# High_Voltage_H-Bridge.net
KiCad netlist of a schematic drawn in Altium Designer
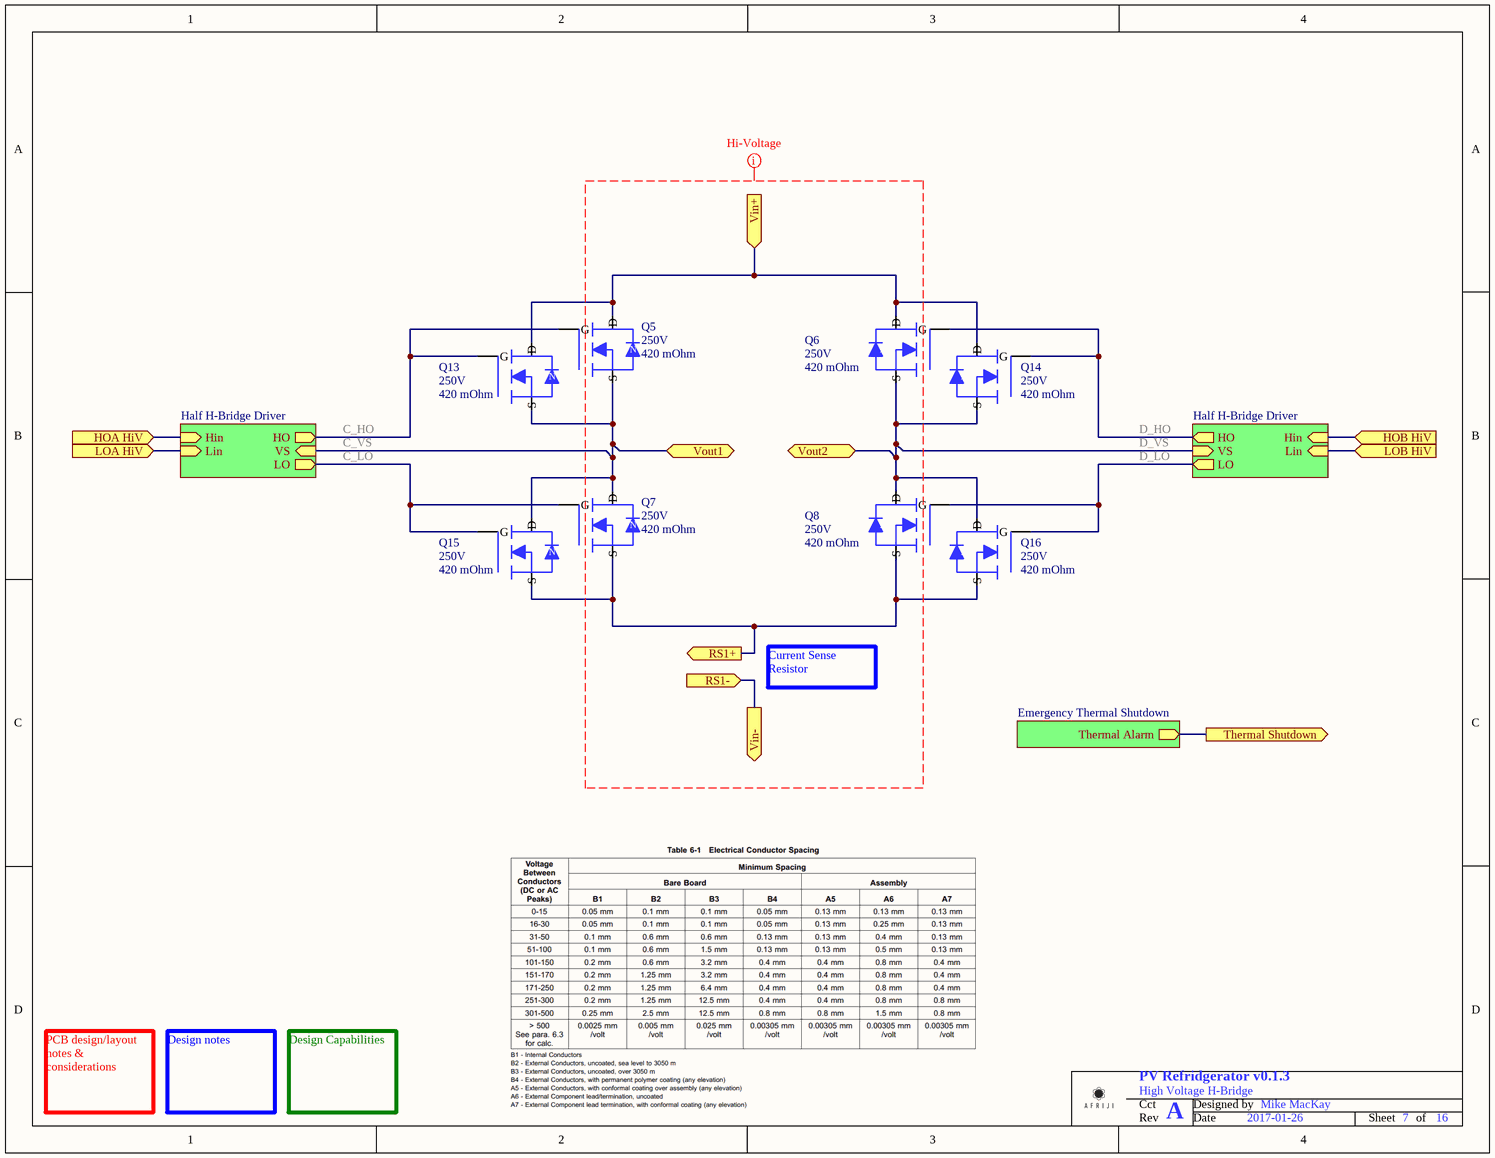
[diagram p0: High Voltage H-Bridge.SchDoc]

(export (version "E")
  (design (tool "Eeschema 10.0.6"))
  (components
    (comp (ref "Q5")
      (value "N-MOSFET 420mR 250V")
      (footprint "DPAK")
      (fields
        (field (name "MANUFACTURER") "Fairchild/ON Semiconductor")
        (field (name "MANUFACTURER PART NUMBER") "FQD9N25TM")
        (field (name "DRAIN TO SOURCE VOLTAGE (VDSS)") "250V")
        (field (name "RDS ON (MAX) @ ID, VGS") "420 mOhm")
      )
      (libsource (lib "Local Library") (part "N-MOSFET 420mR 250V"))
    )
    (comp (ref "Q6")
      (value "N-MOSFET 420mR 250V")
      (footprint "DPAK")
      (fields
        (field (name "MANUFACTURER") "Fairchild/ON Semiconductor")
        (field (name "MANUFACTURER PART NUMBER") "FQD9N25TM")
        (field (name "DRAIN TO SOURCE VOLTAGE (VDSS)") "250V")
        (field (name "RDS ON (MAX) @ ID, VGS") "420 mOhm")
      )
      (libsource (lib "Local Library") (part "N-MOSFET 420mR 250V"))
    )
    (comp (ref "Q7")
      (value "N-MOSFET 420mR 250V")
      (footprint "DPAK")
      (fields
        (field (name "MANUFACTURER") "Fairchild/ON Semiconductor")
        (field (name "MANUFACTURER PART NUMBER") "FQD9N25TM")
        (field (name "DRAIN TO SOURCE VOLTAGE (VDSS)") "250V")
        (field (name "RDS ON (MAX) @ ID, VGS") "420 mOhm")
      )
      (libsource (lib "Local Library") (part "N-MOSFET 420mR 250V"))
    )
    (comp (ref "Q8")
      (value "N-MOSFET 420mR 250V")
      (footprint "DPAK")
      (fields
        (field (name "MANUFACTURER") "Fairchild/ON Semiconductor")
        (field (name "MANUFACTURER PART NUMBER") "FQD9N25TM")
        (field (name "DRAIN TO SOURCE VOLTAGE (VDSS)") "250V")
        (field (name "RDS ON (MAX) @ ID, VGS") "420 mOhm")
      )
      (libsource (lib "Local Library") (part "N-MOSFET 420mR 250V"))
    )
    (comp (ref "Q13")
      (value "N-MOSFET 420mR 250V")
      (footprint "DPAK")
      (fields
        (field (name "MANUFACTURER") "Fairchild/ON Semiconductor")
        (field (name "MANUFACTURER PART NUMBER") "FQD9N25TM")
        (field (name "DRAIN TO SOURCE VOLTAGE (VDSS)") "250V")
        (field (name "RDS ON (MAX) @ ID, VGS") "420 mOhm")
      )
      (libsource (lib "Local Library") (part "N-MOSFET 420mR 250V"))
    )
    (comp (ref "Q14")
      (value "N-MOSFET 420mR 250V")
      (footprint "DPAK")
      (fields
        (field (name "MANUFACTURER") "Fairchild/ON Semiconductor")
        (field (name "MANUFACTURER PART NUMBER") "FQD9N25TM")
        (field (name "DRAIN TO SOURCE VOLTAGE (VDSS)") "250V")
        (field (name "RDS ON (MAX) @ ID, VGS") "420 mOhm")
      )
      (libsource (lib "Local Library") (part "N-MOSFET 420mR 250V"))
    )
    (comp (ref "Q15")
      (value "N-MOSFET 420mR 250V")
      (footprint "DPAK")
      (fields
        (field (name "MANUFACTURER") "Fairchild/ON Semiconductor")
        (field (name "MANUFACTURER PART NUMBER") "FQD9N25TM")
        (field (name "DRAIN TO SOURCE VOLTAGE (VDSS)") "250V")
        (field (name "RDS ON (MAX) @ ID, VGS") "420 mOhm")
      )
      (libsource (lib "Local Library") (part "N-MOSFET 420mR 250V"))
    )
    (comp (ref "Q16")
      (value "N-MOSFET 420mR 250V")
      (footprint "DPAK")
      (fields
        (field (name "MANUFACTURER") "Fairchild/ON Semiconductor")
        (field (name "MANUFACTURER PART NUMBER") "FQD9N25TM")
        (field (name "DRAIN TO SOURCE VOLTAGE (VDSS)") "250V")
        (field (name "RDS ON (MAX) @ ID, VGS") "420 mOhm")
      )
      (libsource (lib "Local Library") (part "N-MOSFET 420mR 250V"))
    )
  )
  (nets
    (net (code "1") (name "/C_HO") (class "Default")
      (node (ref "Q13") (pin "1") (pinfunction "G_1") (pintype "passive"))
      (node (ref "Q5") (pin "1") (pinfunction "G_1") (pintype "passive"))
    )
    (net (code "2") (name "/C_LO") (class "Default")
      (node (ref "Q15") (pin "1") (pinfunction "G_1") (pintype "passive"))
      (node (ref "Q7") (pin "1") (pinfunction "G_1") (pintype "passive"))
    )
    (net (code "3") (name "/C_VS") (class "Default")
      (node (ref "Q13") (pin "3") (pinfunction "S_3") (pintype "passive"))
      (node (ref "Q15") (pin "2") (pinfunction "D_2") (pintype "passive"))
      (node (ref "Q5") (pin "3") (pinfunction "S_3") (pintype "passive"))
      (node (ref "Q7") (pin "2") (pinfunction "D_2") (pintype "passive"))
    )
    (net (code "4") (name "/D_HO") (class "Default")
      (node (ref "Q14") (pin "1") (pinfunction "G_1") (pintype "passive"))
      (node (ref "Q6") (pin "1") (pinfunction "G_1") (pintype "passive"))
    )
    (net (code "5") (name "/D_LO") (class "Default")
      (node (ref "Q16") (pin "1") (pinfunction "G_1") (pintype "passive"))
      (node (ref "Q8") (pin "1") (pinfunction "G_1") (pintype "passive"))
    )
    (net (code "6") (name "/D_VS") (class "Default")
      (node (ref "Q14") (pin "3") (pinfunction "S_3") (pintype "passive"))
      (node (ref "Q16") (pin "2") (pinfunction "D_2") (pintype "passive"))
      (node (ref "Q6") (pin "3") (pinfunction "S_3") (pintype "passive"))
      (node (ref "Q8") (pin "2") (pinfunction "D_2") (pintype "passive"))
    )
    (net (code "11") (name "/RS1+") (class "Default")
      (node (ref "Q15") (pin "3") (pinfunction "S_3") (pintype "passive"))
      (node (ref "Q16") (pin "3") (pinfunction "S_3") (pintype "passive"))
      (node (ref "Q7") (pin "3") (pinfunction "S_3") (pintype "passive"))
      (node (ref "Q8") (pin "3") (pinfunction "S_3") (pintype "passive"))
    )
    (net (code "14") (name "/Vin+") (class "Default")
      (node (ref "Q13") (pin "2") (pinfunction "D_2") (pintype "passive"))
      (node (ref "Q14") (pin "2") (pinfunction "D_2") (pintype "passive"))
      (node (ref "Q5") (pin "2") (pinfunction "D_2") (pintype "passive"))
      (node (ref "Q6") (pin "2") (pinfunction "D_2") (pintype "passive"))
    )
  )
)
